# talkie_module_1_0.net
KiCad netlist of a schematic drawn in EAGLE
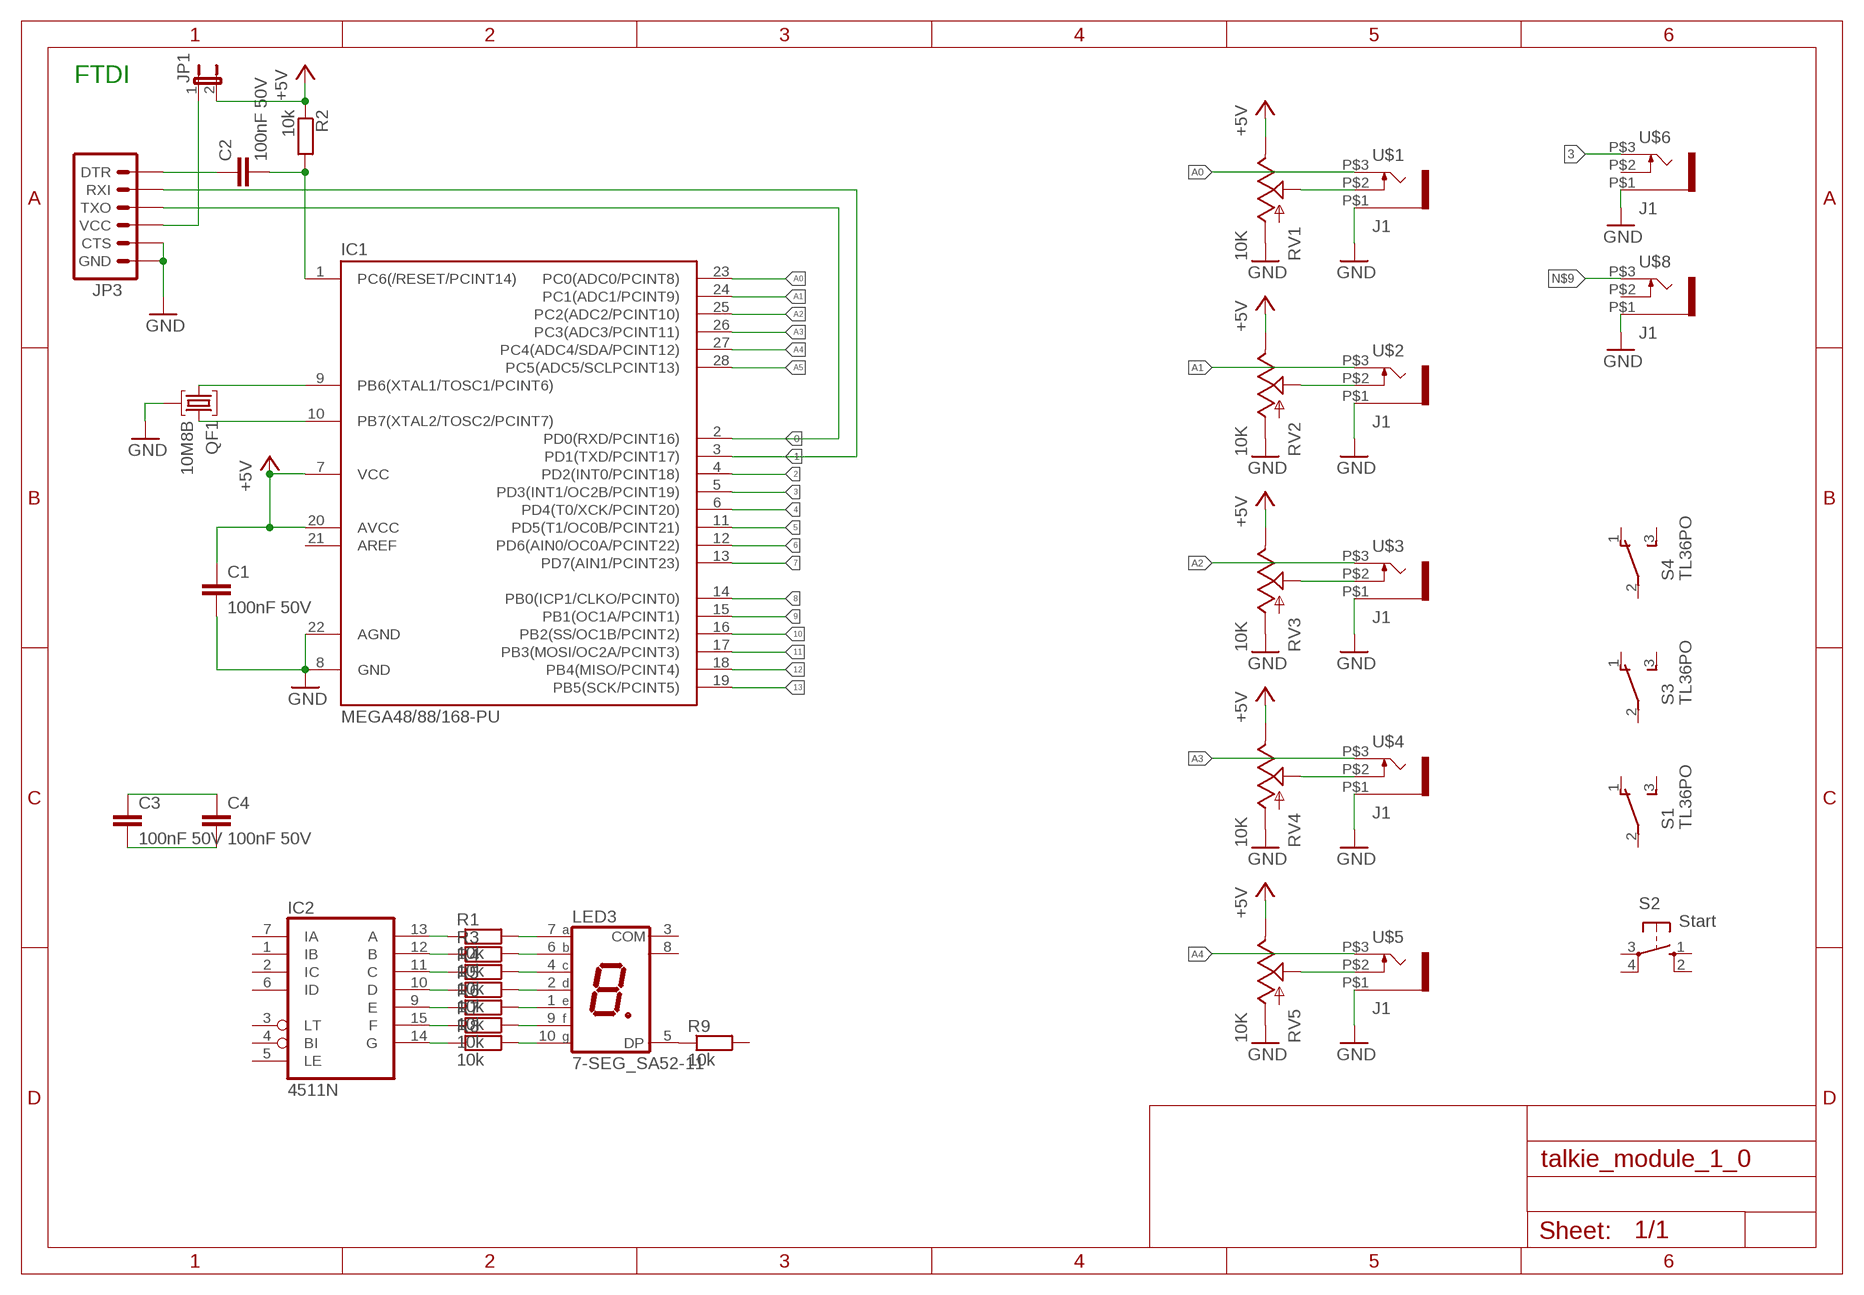
[diagram p0: schematic, sheet 1]

(export (version "E")
  (design (tool "Eeschema 10.0.6"))
  (components
    (comp (ref "C1")
      (value "100nF 50V")
      (footprint "eagle-import:C025-025X050")
      (libsource (lib "eagle-import") (part "C-EU025-025X050"))
    )
    (comp (ref "C2")
      (value "100nF 50V")
      (footprint "eagle-import:C025-025X050")
      (libsource (lib "eagle-import") (part "C-EU025-025X050"))
    )
    (comp (ref "C3")
      (value "100nF 50V")
      (footprint "eagle-import:C025-025X050")
      (libsource (lib "eagle-import") (part "C-EU025-025X050"))
    )
    (comp (ref "C4")
      (value "100nF 50V")
      (footprint "eagle-import:C025-025X050")
      (libsource (lib "eagle-import") (part "C-EU025-025X050"))
    )
    (comp (ref "IC1")
      (value "MEGA48/88/168-PU")
      (footprint "eagle-import:DIL28-3")
      (libsource (lib "eagle-import") (part "MEGA48/88/168-PU"))
    )
    (comp (ref "IC2")
      (value "4511N")
      (footprint "eagle-import:DIL16")
      (libsource (lib "eagle-import") (part "4511N"))
    )
    (comp (ref "JP1")
      (value "JP1E")
      (footprint "eagle-import:JP1")
      (libsource (lib "eagle-import") (part "JP1E"))
    )
    (comp (ref "JP3")
      (value "ARDUINO_SERIAL_PROGRAMLOCK")
      (footprint "eagle-import:1X06_LOCK")
      (libsource (lib "eagle-import") (part "ARDUINO_SERIAL_PROGRAMLOCK"))
    )
    (comp (ref "LED3")
      (value "7-SEG_SA52-11")
      (footprint "eagle-import:SA52-11")
      (fields (field (name "OC_FARNELL") "1168602"))
      (libsource (lib "eagle-import") (part "7-SEG_SA52-11"))
    )
    (comp (ref "QF1")
      (value "10M8B")
      (footprint "eagle-import:HC49U")
      (libsource (lib "eagle-import") (part "10MB8"))
    )
    (comp (ref "R1")
      (value "10k")
      (footprint "eagle-import:RES-AXIAL-0.4")
      (libsource (lib "eagle-import") (part "RESISTOR"))
    )
    (comp (ref "R2")
      (value "10k")
      (footprint "eagle-import:RES-AXIAL-0.4")
      (libsource (lib "eagle-import") (part "RESISTOR"))
    )
    (comp (ref "R3")
      (value "10k")
      (footprint "eagle-import:RES-AXIAL-0.4")
      (libsource (lib "eagle-import") (part "RESISTOR"))
    )
    (comp (ref "R4")
      (value "10k")
      (footprint "eagle-import:RES-AXIAL-0.4")
      (libsource (lib "eagle-import") (part "RESISTOR"))
    )
    (comp (ref "R5")
      (value "10k")
      (footprint "eagle-import:RES-AXIAL-0.4")
      (libsource (lib "eagle-import") (part "RESISTOR"))
    )
    (comp (ref "R6")
      (value "10k")
      (footprint "eagle-import:RES-AXIAL-0.4")
      (libsource (lib "eagle-import") (part "RESISTOR"))
    )
    (comp (ref "R7")
      (value "10k")
      (footprint "eagle-import:RES-AXIAL-0.4")
      (libsource (lib "eagle-import") (part "RESISTOR"))
    )
    (comp (ref "R8")
      (value "10k")
      (footprint "eagle-import:RES-AXIAL-0.4")
      (libsource (lib "eagle-import") (part "RESISTOR"))
    )
    (comp (ref "R9")
      (value "10k")
      (footprint "eagle-import:RES-AXIAL-0.4")
      (libsource (lib "eagle-import") (part "RESISTOR"))
    )
    (comp (ref "RV1")
      (value "10K")
      (footprint "eagle-import:ALPS_POT")
      (libsource (lib "eagle-import") (part "POT"))
    )
    (comp (ref "RV2")
      (value "10K")
      (footprint "eagle-import:ALPS_POT")
      (libsource (lib "eagle-import") (part "POT"))
    )
    (comp (ref "RV3")
      (value "10K")
      (footprint "eagle-import:ALPS_POT")
      (libsource (lib "eagle-import") (part "POT"))
    )
    (comp (ref "RV4")
      (value "10K")
      (footprint "eagle-import:ALPS_POT")
      (libsource (lib "eagle-import") (part "POT"))
    )
    (comp (ref "RV5")
      (value "10K")
      (footprint "eagle-import:ALPS_POT")
      (libsource (lib "eagle-import") (part "POT"))
    )
    (comp (ref "S1")
      (value "TL36PO")
      (footprint "eagle-import:TL3XPO")
      (libsource (lib "eagle-import") (part "TL36PO"))
    )
    (comp (ref "S2")
      (value "Start")
      (footprint "eagle-import:B3F-10XX")
      (fields (field (name "MPN") "B3F-1000"))
      (libsource (lib "eagle-import") (part "10-XX"))
    )
    (comp (ref "S3")
      (value "TL36PO")
      (footprint "eagle-import:TL3XPO")
      (libsource (lib "eagle-import") (part "TL36PO"))
    )
    (comp (ref "S4")
      (value "TL36PO")
      (footprint "eagle-import:TL3XPO")
      (libsource (lib "eagle-import") (part "TL36PO"))
    )
    (comp (ref "U$1")
      (value "J1")
      (footprint "eagle-import:THONKICONN")
      (libsource (lib "eagle-import") (part "THONKICONN"))
    )
    (comp (ref "U$2")
      (value "J1")
      (footprint "eagle-import:THONKICONN")
      (libsource (lib "eagle-import") (part "THONKICONN"))
    )
    (comp (ref "U$3")
      (value "J1")
      (footprint "eagle-import:THONKICONN")
      (libsource (lib "eagle-import") (part "THONKICONN"))
    )
    (comp (ref "U$4")
      (value "J1")
      (footprint "eagle-import:THONKICONN")
      (libsource (lib "eagle-import") (part "THONKICONN"))
    )
    (comp (ref "U$5")
      (value "J1")
      (footprint "eagle-import:THONKICONN")
      (libsource (lib "eagle-import") (part "THONKICONN"))
    )
    (comp (ref "U$6")
      (value "J1")
      (footprint "eagle-import:THONKICONN")
      (libsource (lib "eagle-import") (part "THONKICONN"))
    )
    (comp (ref "U$8")
      (value "J1")
      (footprint "eagle-import:THONKICONN")
      (libsource (lib "eagle-import") (part "THONKICONN"))
    )
  )
  (nets
    (net (code "1") (name "+5V") (class "Default")
      (node (ref "C1") (pin "1") (pinfunction "1_1") (pintype "passive"))
      (node (ref "IC1") (pin "20") (pinfunction "AVCC_20") (pintype "passive"))
      (node (ref "IC1") (pin "7") (pinfunction "VCC_7") (pintype "power_in"))
      (node (ref "JP1") (pin "2") (pinfunction "2_2") (pintype "passive"))
      (node (ref "R2") (pin "P$1") (pinfunction "1_P$1") (pintype "passive"))
      (node (ref "RV1") (pin "P$1") (pinfunction "E_P$1") (pintype "passive"))
      (node (ref "RV2") (pin "P$1") (pinfunction "E_P$1") (pintype "passive"))
      (node (ref "RV3") (pin "P$1") (pinfunction "E_P$1") (pintype "passive"))
      (node (ref "RV4") (pin "P$1") (pinfunction "E_P$1") (pintype "passive"))
      (node (ref "RV5") (pin "P$1") (pinfunction "E_P$1") (pintype "passive"))
    )
    (net (code "2") (name "0") (class "Default")
      (node (ref "IC1") (pin "2") (pinfunction "PD0(RXD/PCINT16)_2") (pintype "bidirectional"))
      (node (ref "JP3") (pin "3") (pinfunction "TXO_3") (pintype "passive"))
    )
    (net (code "3") (name "1") (class "Default")
      (node (ref "IC1") (pin "3") (pinfunction "PD1(TXD/PCINT17)_3") (pintype "bidirectional"))
      (node (ref "JP3") (pin "2") (pinfunction "RXI_2") (pintype "passive"))
    )
    (net (code "4") (name "2") (class "Default")
      (node (ref "IC1") (pin "4") (pinfunction "PD2(INT0/PCINT18)_4") (pintype "bidirectional"))
    )
    (net (code "5") (name "3") (class "Default")
      (node (ref "IC1") (pin "5") (pinfunction "PD3(INT1/OC2B/PCINT19)_5") (pintype "bidirectional"))
      (node (ref "U$6") (pin "P$3") (pinfunction "3_P$3") (pintype "passive"))
    )
    (net (code "6") (name "4") (class "Default")
      (node (ref "IC1") (pin "6") (pinfunction "PD4(T0/XCK/PCINT20)_6") (pintype "bidirectional"))
    )
    (net (code "7") (name "5") (class "Default")
      (node (ref "IC1") (pin "11") (pinfunction "PD5(T1/OC0B/PCINT21)_11") (pintype "bidirectional"))
    )
    (net (code "8") (name "6") (class "Default")
      (node (ref "IC1") (pin "12") (pinfunction "PD6(AIN0/OC0A/PCINT22)_12") (pintype "bidirectional"))
    )
    (net (code "9") (name "7") (class "Default")
      (node (ref "IC1") (pin "13") (pinfunction "PD7(AIN1/PCINT23)_13") (pintype "bidirectional"))
    )
    (net (code "10") (name "8") (class "Default")
      (node (ref "IC1") (pin "14") (pinfunction "PB0(ICP1/CLKO/PCINT0)_14") (pintype "bidirectional"))
    )
    (net (code "11") (name "9") (class "Default")
      (node (ref "IC1") (pin "15") (pinfunction "PB1(OC1A/PCINT1)_15") (pintype "bidirectional"))
    )
    (net (code "12") (name "10") (class "Default")
      (node (ref "IC1") (pin "16") (pinfunction "PB2(SS/OC1B/PCINT2)_16") (pintype "bidirectional"))
    )
    (net (code "13") (name "11") (class "Default")
      (node (ref "IC1") (pin "17") (pinfunction "PB3(MOSI/OC2A/PCINT3)_17") (pintype "bidirectional"))
    )
    (net (code "14") (name "12") (class "Default")
      (node (ref "IC1") (pin "18") (pinfunction "PB4(MISO/PCINT4)_18") (pintype "bidirectional"))
    )
    (net (code "15") (name "13") (class "Default")
      (node (ref "IC1") (pin "19") (pinfunction "PB5(SCK/PCINT5)_19") (pintype "bidirectional"))
    )
    (net (code "16") (name "A0") (class "Default")
      (node (ref "IC1") (pin "23") (pinfunction "PC0(ADC0/PCINT8)_23") (pintype "bidirectional"))
      (node (ref "U$1") (pin "P$3") (pinfunction "3_P$3") (pintype "passive"))
    )
    (net (code "17") (name "A1") (class "Default")
      (node (ref "IC1") (pin "24") (pinfunction "PC1(ADC1/PCINT9)_24") (pintype "bidirectional"))
      (node (ref "U$2") (pin "P$3") (pinfunction "3_P$3") (pintype "passive"))
    )
    (net (code "18") (name "A2") (class "Default")
      (node (ref "IC1") (pin "25") (pinfunction "PC2(ADC2/PCINT10)_25") (pintype "bidirectional"))
      (node (ref "U$3") (pin "P$3") (pinfunction "3_P$3") (pintype "passive"))
    )
    (net (code "19") (name "A3") (class "Default")
      (node (ref "IC1") (pin "26") (pinfunction "PC3(ADC3/PCINT11)_26") (pintype "bidirectional"))
      (node (ref "U$4") (pin "P$3") (pinfunction "3_P$3") (pintype "passive"))
    )
    (net (code "20") (name "A4") (class "Default")
      (node (ref "IC1") (pin "27") (pinfunction "PC4(ADC4/SDA/PCINT12)_27") (pintype "bidirectional"))
      (node (ref "U$5") (pin "P$3") (pinfunction "3_P$3") (pintype "passive"))
    )
    (net (code "21") (name "A5") (class "Default")
      (node (ref "IC1") (pin "28") (pinfunction "PC5(ADC5/SCLPCINT13)_28") (pintype "bidirectional"))
    )
    (net (code "22") (name "GND") (class "Default")
      (node (ref "C1") (pin "2") (pinfunction "2_2") (pintype "passive"))
      (node (ref "IC1") (pin "22") (pinfunction "AGND_22") (pintype "power_in"))
      (node (ref "IC1") (pin "8") (pinfunction "GND_8") (pintype "power_in"))
      (node (ref "JP3") (pin "5") (pinfunction "CTS_5") (pintype "passive"))
      (node (ref "JP3") (pin "6") (pinfunction "GND_6") (pintype "passive"))
      (node (ref "QF1") (pin "2") (pinfunction "2_2") (pintype "passive"))
      (node (ref "RV1") (pin "P$3") (pinfunction "A_P$3") (pintype "passive"))
      (node (ref "RV2") (pin "P$3") (pinfunction "A_P$3") (pintype "passive"))
      (node (ref "RV3") (pin "P$3") (pinfunction "A_P$3") (pintype "passive"))
      (node (ref "RV4") (pin "P$3") (pinfunction "A_P$3") (pintype "passive"))
      (node (ref "RV5") (pin "P$3") (pinfunction "A_P$3") (pintype "passive"))
      (node (ref "U$1") (pin "P$1") (pinfunction "5_P$1") (pintype "passive"))
      (node (ref "U$2") (pin "P$1") (pinfunction "5_P$1") (pintype "passive"))
      (node (ref "U$3") (pin "P$1") (pinfunction "5_P$1") (pintype "passive"))
      (node (ref "U$4") (pin "P$1") (pinfunction "5_P$1") (pintype "passive"))
      (node (ref "U$5") (pin "P$1") (pinfunction "5_P$1") (pintype "passive"))
      (node (ref "U$6") (pin "P$1") (pinfunction "5_P$1") (pintype "passive"))
      (node (ref "U$8") (pin "P$1") (pinfunction "5_P$1") (pintype "passive"))
    )
    (net (code "23") (name "N$9") (class "Default")
      (node (ref "U$8") (pin "P$3") (pinfunction "3_P$3") (pintype "passive"))
    )
    (net (code "24") (name "Net-(C3-Pad1)") (class "Default")
      (node (ref "C3") (pin "1") (pinfunction "1_1") (pintype "passive"))
      (node (ref "C4") (pin "1") (pinfunction "1_1") (pintype "passive"))
    )
    (net (code "25") (name "Net-(C3-Pad2)") (class "Default")
      (node (ref "C3") (pin "2") (pinfunction "2_2") (pintype "passive"))
      (node (ref "C4") (pin "2") (pinfunction "2_2") (pintype "passive"))
    )
    (net (code "26") (name "Net-(IC1-PB6(XTAL1{slash}TOSC1{slash}PCINT6))") (class "Default")
      (node (ref "IC1") (pin "9") (pinfunction "PB6(XTAL1/TOSC1/PCINT6)_9") (pintype "bidirectional"))
      (node (ref "QF1") (pin "1") (pinfunction "1_1") (pintype "passive"))
    )
    (net (code "27") (name "Net-(IC1-PB7(XTAL2{slash}TOSC2{slash}PCINT7))") (class "Default")
      (node (ref "IC1") (pin "10") (pinfunction "PB7(XTAL2/TOSC2/PCINT7)_10") (pintype "bidirectional"))
      (node (ref "QF1") (pin "3") (pinfunction "3_3") (pintype "passive"))
    )
    (net (code "28") (name "Net-(IC1-PC6({slash}RESET{slash}PCINT14))") (class "Default")
      (node (ref "C2") (pin "2") (pinfunction "2_2") (pintype "passive"))
      (node (ref "IC1") (pin "1") (pinfunction "PC6(/RESET/PCINT14)_1") (pintype "bidirectional"))
      (node (ref "R2") (pin "P$2") (pinfunction "2_P$2") (pintype "passive"))
    )
    (net (code "29") (name "Net-(IC2A-A)") (class "Default")
      (node (ref "IC2") (pin "13") (pinfunction "A_13") (pintype "output"))
      (node (ref "R1") (pin "P$1") (pinfunction "1_P$1") (pintype "passive"))
    )
    (net (code "30") (name "Net-(IC2A-B)") (class "Default")
      (node (ref "IC2") (pin "12") (pinfunction "B_12") (pintype "output"))
      (node (ref "R3") (pin "P$1") (pinfunction "1_P$1") (pintype "passive"))
    )
    (net (code "31") (name "Net-(IC2A-C)") (class "Default")
      (node (ref "IC2") (pin "11") (pinfunction "C_11") (pintype "output"))
      (node (ref "R4") (pin "P$1") (pinfunction "1_P$1") (pintype "passive"))
    )
    (net (code "32") (name "Net-(IC2A-D)") (class "Default")
      (node (ref "IC2") (pin "10") (pinfunction "D_10") (pintype "output"))
      (node (ref "R5") (pin "P$1") (pinfunction "1_P$1") (pintype "passive"))
    )
    (net (code "33") (name "Net-(IC2A-E)") (class "Default")
      (node (ref "IC2") (pin "9") (pinfunction "E_9") (pintype "output"))
      (node (ref "R6") (pin "P$1") (pinfunction "1_P$1") (pintype "passive"))
    )
    (net (code "34") (name "Net-(IC2A-F)") (class "Default")
      (node (ref "IC2") (pin "15") (pinfunction "F_15") (pintype "output"))
      (node (ref "R7") (pin "P$1") (pinfunction "1_P$1") (pintype "passive"))
    )
    (net (code "35") (name "Net-(IC2A-G)") (class "Default")
      (node (ref "IC2") (pin "14") (pinfunction "G_14") (pintype "output"))
      (node (ref "R8") (pin "P$1") (pinfunction "1_P$1") (pintype "passive"))
    )
    (net (code "36") (name "Net-(JP3-DTR)") (class "Default")
      (node (ref "C2") (pin "1") (pinfunction "1_1") (pintype "passive"))
      (node (ref "JP3") (pin "1") (pinfunction "DTR_1") (pintype "passive"))
    )
    (net (code "37") (name "Net-(JP3-VCC)") (class "Default")
      (node (ref "JP1") (pin "1") (pinfunction "1_1") (pintype "passive"))
      (node (ref "JP3") (pin "4") (pinfunction "VCC_4") (pintype "passive"))
    )
    (net (code "38") (name "Net-(LED3-A)") (class "Default")
      (node (ref "LED3") (pin "7") (pinfunction "A_7") (pintype "passive"))
      (node (ref "R1") (pin "P$2") (pinfunction "2_P$2") (pintype "passive"))
    )
    (net (code "39") (name "Net-(LED3-B)") (class "Default")
      (node (ref "LED3") (pin "6") (pinfunction "B_6") (pintype "passive"))
      (node (ref "R3") (pin "P$2") (pinfunction "2_P$2") (pintype "passive"))
    )
    (net (code "40") (name "Net-(LED3-C)") (class "Default")
      (node (ref "LED3") (pin "4") (pinfunction "C_4") (pintype "passive"))
      (node (ref "R4") (pin "P$2") (pinfunction "2_P$2") (pintype "passive"))
    )
    (net (code "41") (name "Net-(LED3-D)") (class "Default")
      (node (ref "LED3") (pin "2") (pinfunction "D_2") (pintype "passive"))
      (node (ref "R5") (pin "P$2") (pinfunction "2_P$2") (pintype "passive"))
    )
    (net (code "42") (name "Net-(LED3-DP)") (class "Default")
      (node (ref "LED3") (pin "5") (pinfunction "DP_5") (pintype "passive"))
      (node (ref "R9") (pin "P$1") (pinfunction "1_P$1") (pintype "passive"))
    )
    (net (code "43") (name "Net-(LED3-E)") (class "Default")
      (node (ref "LED3") (pin "1") (pinfunction "E_1") (pintype "passive"))
      (node (ref "R6") (pin "P$2") (pinfunction "2_P$2") (pintype "passive"))
    )
    (net (code "44") (name "Net-(LED3-F)") (class "Default")
      (node (ref "LED3") (pin "9") (pinfunction "F_9") (pintype "passive"))
      (node (ref "R7") (pin "P$2") (pinfunction "2_P$2") (pintype "passive"))
    )
    (net (code "45") (name "Net-(LED3-G)") (class "Default")
      (node (ref "LED3") (pin "10") (pinfunction "G_10") (pintype "passive"))
      (node (ref "R8") (pin "P$2") (pinfunction "2_P$2") (pintype "passive"))
    )
    (net (code "46") (name "Net-(RV1-S)") (class "Default")
      (node (ref "RV1") (pin "P$2") (pinfunction "S_P$2") (pintype "passive"))
      (node (ref "U$1") (pin "P$2") (pinfunction "4_P$2") (pintype "passive"))
    )
    (net (code "47") (name "Net-(RV2-S)") (class "Default")
      (node (ref "RV2") (pin "P$2") (pinfunction "S_P$2") (pintype "passive"))
      (node (ref "U$2") (pin "P$2") (pinfunction "4_P$2") (pintype "passive"))
    )
    (net (code "48") (name "Net-(RV3-S)") (class "Default")
      (node (ref "RV3") (pin "P$2") (pinfunction "S_P$2") (pintype "passive"))
      (node (ref "U$3") (pin "P$2") (pinfunction "4_P$2") (pintype "passive"))
    )
    (net (code "49") (name "Net-(RV4-S)") (class "Default")
      (node (ref "RV4") (pin "P$2") (pinfunction "S_P$2") (pintype "passive"))
      (node (ref "U$4") (pin "P$2") (pinfunction "4_P$2") (pintype "passive"))
    )
    (net (code "50") (name "Net-(RV5-S)") (class "Default")
      (node (ref "RV5") (pin "P$2") (pinfunction "S_P$2") (pintype "passive"))
      (node (ref "U$5") (pin "P$2") (pinfunction "4_P$2") (pintype "passive"))
    )
    (net (code "51") (name "unconnected-(IC1-AREF-Pad21)") (class "Default")
      (node (ref "IC1") (pin "21") (pinfunction "AREF_21") (pintype "passive"))
    )
    (net (code "52") (name "unconnected-(IC2A-BI-Pad4)") (class "Default")
      (node (ref "IC2") (pin "4") (pinfunction "BI_4") (pintype "input"))
    )
    (net (code "53") (name "unconnected-(IC2A-IA-Pad7)") (class "Default")
      (node (ref "IC2") (pin "7") (pinfunction "IA_7") (pintype "input"))
    )
    (net (code "54") (name "unconnected-(IC2A-IB-Pad1)") (class "Default")
      (node (ref "IC2") (pin "1") (pinfunction "IB_1") (pintype "input"))
    )
    (net (code "55") (name "unconnected-(IC2A-IC-Pad2)") (class "Default")
      (node (ref "IC2") (pin "2") (pinfunction "IC_2") (pintype "input"))
    )
    (net (code "56") (name "unconnected-(IC2A-ID-Pad6)") (class "Default")
      (node (ref "IC2") (pin "6") (pinfunction "ID_6") (pintype "input"))
    )
    (net (code "57") (name "unconnected-(IC2A-LE-Pad5)") (class "Default")
      (node (ref "IC2") (pin "5") (pinfunction "LE_5") (pintype "input"))
    )
    (net (code "58") (name "unconnected-(IC2A-LT-Pad3)") (class "Default")
      (node (ref "IC2") (pin "3") (pinfunction "LT_3") (pintype "input"))
    )
    (net (code "59") (name "unconnected-(LED3-COM-Pad3)") (class "Default")
      (node (ref "LED3") (pin "3") (pinfunction "COM_3") (pintype "passive"))
    )
    (net (code "60") (name "unconnected-(LED3-COM-Pad8)") (class "Default")
      (node (ref "LED3") (pin "8") (pinfunction "COM_8") (pintype "passive"))
    )
    (net (code "61") (name "unconnected-(R9-2-PadP$2)") (class "Default")
      (node (ref "R9") (pin "P$2") (pinfunction "2_P$2") (pintype "passive"))
    )
    (net (code "62") (name "unconnected-(S1-O-Pad1)") (class "Default")
      (node (ref "S1") (pin "1") (pinfunction "O_1") (pintype "passive"))
    )
    (net (code "63") (name "unconnected-(S1-P-Pad2)") (class "Default")
      (node (ref "S1") (pin "2") (pinfunction "P_2") (pintype "passive"))
    )
    (net (code "64") (name "unconnected-(S1-S-Pad3)") (class "Default")
      (node (ref "S1") (pin "3") (pinfunction "S_3") (pintype "passive"))
    )
    (net (code "65") (name "unconnected-(S2-P-Pad3)") (class "Default")
      (node (ref "S2") (pin "3") (pinfunction "P_3") (pintype "passive"))
    )
    (net (code "66") (name "unconnected-(S2-P1-Pad4)") (class "Default")
      (node (ref "S2") (pin "4") (pinfunction "P1_4") (pintype "passive"))
    )
    (net (code "67") (name "unconnected-(S2-S-Pad1)") (class "Default")
      (node (ref "S2") (pin "1") (pinfunction "S_1") (pintype "passive"))
    )
    (net (code "68") (name "unconnected-(S2-S1-Pad2)") (class "Default")
      (node (ref "S2") (pin "2") (pinfunction "S1_2") (pintype "passive"))
    )
    (net (code "69") (name "unconnected-(S3-O-Pad1)") (class "Default")
      (node (ref "S3") (pin "1") (pinfunction "O_1") (pintype "passive"))
    )
    (net (code "70") (name "unconnected-(S3-P-Pad2)") (class "Default")
      (node (ref "S3") (pin "2") (pinfunction "P_2") (pintype "passive"))
    )
    (net (code "71") (name "unconnected-(S3-S-Pad3)") (class "Default")
      (node (ref "S3") (pin "3") (pinfunction "S_3") (pintype "passive"))
    )
    (net (code "72") (name "unconnected-(S4-O-Pad1)") (class "Default")
      (node (ref "S4") (pin "1") (pinfunction "O_1") (pintype "passive"))
    )
    (net (code "73") (name "unconnected-(S4-P-Pad2)") (class "Default")
      (node (ref "S4") (pin "2") (pinfunction "P_2") (pintype "passive"))
    )
    (net (code "74") (name "unconnected-(S4-S-Pad3)") (class "Default")
      (node (ref "S4") (pin "3") (pinfunction "S_3") (pintype "passive"))
    )
    (net (code "75") (name "unconnected-(U$6-4-PadP$2)") (class "Default")
      (node (ref "U$6") (pin "P$2") (pinfunction "4_P$2") (pintype "passive"))
    )
    (net (code "76") (name "unconnected-(U$8-4-PadP$2)") (class "Default")
      (node (ref "U$8") (pin "P$2") (pinfunction "4_P$2") (pintype "passive"))
    )
  )
)
